# Lab2.net
KiCad netlist of a schematic drawn in EAGLE
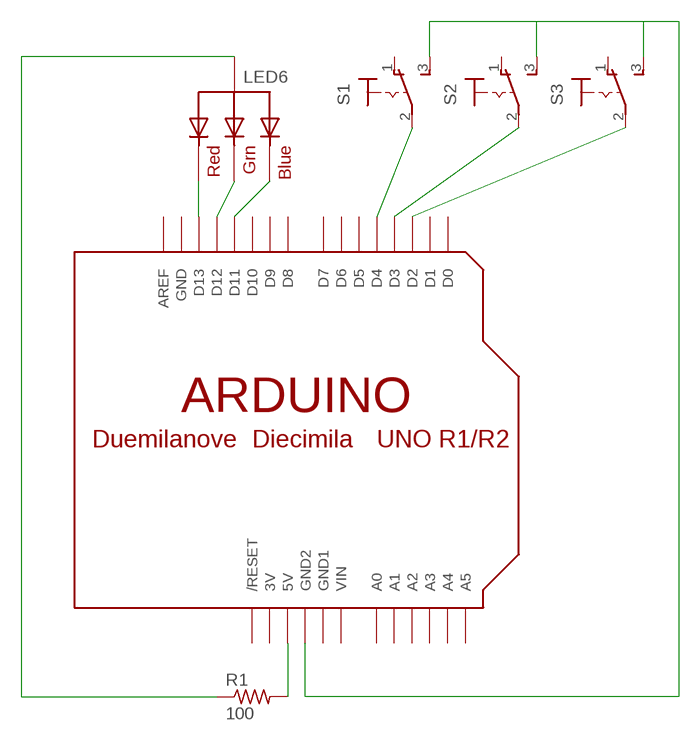
[diagram p0: schematic, sheet 1]

(export (version "E")
  (design (tool "Eeschema 10.0.6"))
  (components
    (comp (ref "LED6")
      (value "RGBLED_CA-5MM")
      (footprint "eagle-import:LED5MMRGB")
      (libsource (lib "eagle-import") (part "RGBLED_CA-5MM"))
    )
    (comp (ref "R1")
      (value "100")
      (footprint "eagle-import:0411_12")
      (libsource (lib "eagle-import") (part "R-US_0411/12"))
    )
    (comp (ref "S1")
      (value "M9040P")
      (footprint "eagle-import:M9040P")
      (libsource (lib "eagle-import") (part "M9040P"))
    )
    (comp (ref "S2")
      (value "M9040P")
      (footprint "eagle-import:M9040P")
      (libsource (lib "eagle-import") (part "M9040P"))
    )
    (comp (ref "S3")
      (value "M9040P")
      (footprint "eagle-import:M9040P")
      (libsource (lib "eagle-import") (part "M9040P"))
    )
    (comp (ref "U$1")
      (value "ARDUINO-BPLACE")
      (footprint "eagle-import:ARDUINO-BPLACE")
      (libsource (lib "eagle-import") (part "ARDUINO-BPLACE"))
    )
  )
  (nets
    (net (code "1") (name "/3V") (class "Default")
      (node (ref "U$1") (pin "3V") (pinfunction "3V_3V") (pintype "power_in"))
    )
    (net (code "2") (name "/GND") (class "Default")
      (node (ref "U$1") (pin "GND") (pinfunction "GND_GND") (pintype "power_in"))
    )
    (net (code "3") (name "/GND1") (class "Default")
      (node (ref "U$1") (pin "GND1") (pinfunction "GND1_GND1") (pintype "power_in"))
    )
    (net (code "4") (name "/VIN") (class "Default")
      (node (ref "U$1") (pin "VIN") (pinfunction "VIN_VIN") (pintype "power_in"))
    )
    (net (code "5") (name "Net-(LED6-BLUE)") (class "Default")
      (node (ref "LED6") (pin "4") (pinfunction "BLUE_4") (pintype "bidirectional"))
      (node (ref "U$1") (pin "D11") (pinfunction "D11_D11") (pintype "bidirectional"))
    )
    (net (code "6") (name "Net-(LED6-GREEN)") (class "Default")
      (node (ref "LED6") (pin "3") (pinfunction "GREEN_3") (pintype "bidirectional"))
      (node (ref "U$1") (pin "D12") (pinfunction "D12_D12") (pintype "bidirectional"))
    )
    (net (code "7") (name "Net-(LED6-RED)") (class "Default")
      (node (ref "LED6") (pin "1") (pinfunction "RED_1") (pintype "bidirectional"))
      (node (ref "U$1") (pin "D13") (pinfunction "D13_D13") (pintype "bidirectional"))
    )
    (net (code "8") (name "Net-(LED6-VCC)") (class "Default")
      (node (ref "LED6") (pin "2") (pinfunction "VCC_2") (pintype "bidirectional"))
      (node (ref "R1") (pin "1") (pinfunction "1_1") (pintype "passive"))
    )
    (net (code "9") (name "Net-(R1-Pad2)") (class "Default")
      (node (ref "R1") (pin "2") (pinfunction "2_2") (pintype "passive"))
      (node (ref "U$1") (pin "5V") (pinfunction "5V_5V") (pintype "power_in"))
    )
    (net (code "10") (name "Net-(S1-P)") (class "Default")
      (node (ref "S1") (pin "2") (pinfunction "P_2") (pintype "passive"))
      (node (ref "U$1") (pin "D4") (pinfunction "D4_D4") (pintype "bidirectional"))
    )
    (net (code "11") (name "Net-(S1-S)") (class "Default")
      (node (ref "S1") (pin "3") (pinfunction "S_3") (pintype "passive"))
      (node (ref "S2") (pin "3") (pinfunction "S_3") (pintype "passive"))
      (node (ref "S3") (pin "3") (pinfunction "S_3") (pintype "passive"))
      (node (ref "U$1") (pin "GND2") (pinfunction "GND2_GND2") (pintype "power_in"))
    )
    (net (code "12") (name "Net-(S2-P)") (class "Default")
      (node (ref "S2") (pin "2") (pinfunction "P_2") (pintype "passive"))
      (node (ref "U$1") (pin "D3") (pinfunction "D3_D3") (pintype "bidirectional"))
    )
    (net (code "13") (name "Net-(S3-P)") (class "Default")
      (node (ref "S3") (pin "2") (pinfunction "P_2") (pintype "passive"))
      (node (ref "U$1") (pin "D2") (pinfunction "D2_D2") (pintype "bidirectional"))
    )
    (net (code "14") (name "unconnected-(S1-O-Pad1)") (class "Default")
      (node (ref "S1") (pin "1") (pinfunction "O_1") (pintype "passive"))
    )
    (net (code "15") (name "unconnected-(S2-O-Pad1)") (class "Default")
      (node (ref "S2") (pin "1") (pinfunction "O_1") (pintype "passive"))
    )
    (net (code "16") (name "unconnected-(S3-O-Pad1)") (class "Default")
      (node (ref "S3") (pin "1") (pinfunction "O_1") (pintype "passive"))
    )
    (net (code "17") (name "unconnected-(U$1-PadA0)") (class "Default")
      (node (ref "U$1") (pin "A0") (pinfunction "A0_A0") (pintype "bidirectional"))
    )
    (net (code "18") (name "unconnected-(U$1-PadA1)") (class "Default")
      (node (ref "U$1") (pin "A1") (pinfunction "A1_A1") (pintype "bidirectional"))
    )
    (net (code "19") (name "unconnected-(U$1-PadA2)") (class "Default")
      (node (ref "U$1") (pin "A2") (pinfunction "A2_A2") (pintype "bidirectional"))
    )
    (net (code "20") (name "unconnected-(U$1-PadA3)") (class "Default")
      (node (ref "U$1") (pin "A3") (pinfunction "A3_A3") (pintype "bidirectional"))
    )
    (net (code "21") (name "unconnected-(U$1-PadA4)") (class "Default")
      (node (ref "U$1") (pin "A4") (pinfunction "A4_A4") (pintype "bidirectional"))
    )
    (net (code "22") (name "unconnected-(U$1-PadA5)") (class "Default")
      (node (ref "U$1") (pin "A5") (pinfunction "A5_A5") (pintype "bidirectional"))
    )
    (net (code "23") (name "unconnected-(U$1-PadAREF)") (class "Default")
      (node (ref "U$1") (pin "AREF") (pinfunction "AREF_AREF") (pintype "bidirectional"))
    )
    (net (code "24") (name "unconnected-(U$1-PadD0)") (class "Default")
      (node (ref "U$1") (pin "D0") (pinfunction "D0_D0") (pintype "bidirectional"))
    )
    (net (code "25") (name "unconnected-(U$1-PadD1)") (class "Default")
      (node (ref "U$1") (pin "D1") (pinfunction "D1_D1") (pintype "bidirectional"))
    )
    (net (code "26") (name "unconnected-(U$1-PadD5)") (class "Default")
      (node (ref "U$1") (pin "D5") (pinfunction "D5_D5") (pintype "bidirectional"))
    )
    (net (code "27") (name "unconnected-(U$1-PadD6)") (class "Default")
      (node (ref "U$1") (pin "D6") (pinfunction "D6_D6") (pintype "bidirectional"))
    )
    (net (code "28") (name "unconnected-(U$1-PadD7)") (class "Default")
      (node (ref "U$1") (pin "D7") (pinfunction "D7_D7") (pintype "bidirectional"))
    )
    (net (code "29") (name "unconnected-(U$1-PadD8)") (class "Default")
      (node (ref "U$1") (pin "D8") (pinfunction "D8_D8") (pintype "bidirectional"))
    )
    (net (code "30") (name "unconnected-(U$1-PadD9)") (class "Default")
      (node (ref "U$1") (pin "D9") (pinfunction "D9_D9") (pintype "bidirectional"))
    )
    (net (code "31") (name "unconnected-(U$1-PadD10)") (class "Default")
      (node (ref "U$1") (pin "D10") (pinfunction "D10_D10") (pintype "bidirectional"))
    )
    (net (code "32") (name "unconnected-(U$1-{slash}RESET-PadRESET)") (class "Default")
      (node (ref "U$1") (pin "RESET") (pinfunction "/RESET_RESET") (pintype "bidirectional"))
    )
  )
)
